# adapter-50-100mil-x2.net
KiCad netlist of a schematic drawn in Altium Designer
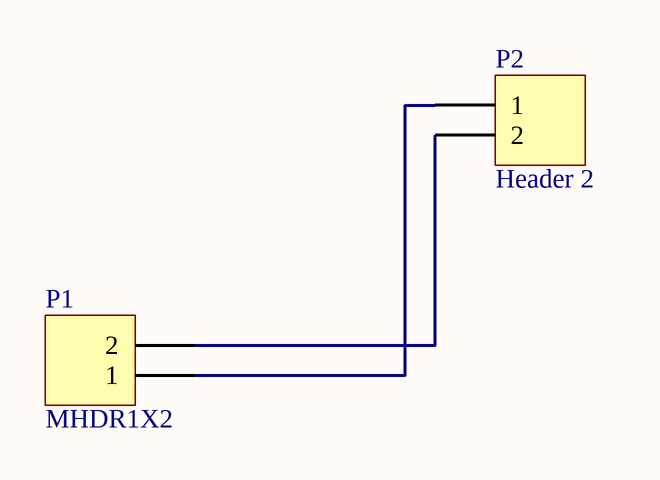
[diagram p0: adapter-50-100mil-x2.SchDoc]

(export (version "E")
  (design (tool "Eeschema 10.0.6"))
  (components
    (comp (ref "P1")
      (value "MHDR1X2")
      (footprint "MHDR1X2")
      (description "Header, 2-Pin")
      (fields (field (name "PUBLISHER") "Altium Limited"))
      (libsource (lib "Miscellaneous Connectors") (part "MHDR1X2"))
    )
    (comp (ref "P2")
      (value "Header 2")
      (footprint "HDR1X2")
      (description "Header, 2-Pin")
      (fields (field (name "PUBLISHER") "Altium Limited"))
      (libsource (lib "Miscellaneous Connectors") (part "Header 2"))
    )
  )
  (nets
    (net (code "1") (name "Net-(P1-Pad1)") (class "Default")
      (node (ref "P1") (pin "1") (pinfunction "1_1") (pintype "passive"))
      (node (ref "P2") (pin "1") (pinfunction "1_1") (pintype "passive"))
    )
    (net (code "2") (name "Net-(P1-Pad2)") (class "Default")
      (node (ref "P1") (pin "2") (pinfunction "2_2") (pintype "passive"))
      (node (ref "P2") (pin "2") (pinfunction "2_2") (pintype "passive"))
    )
  )
)
